# IR-Detector.net
KiCad netlist of a schematic drawn in Altium Designer
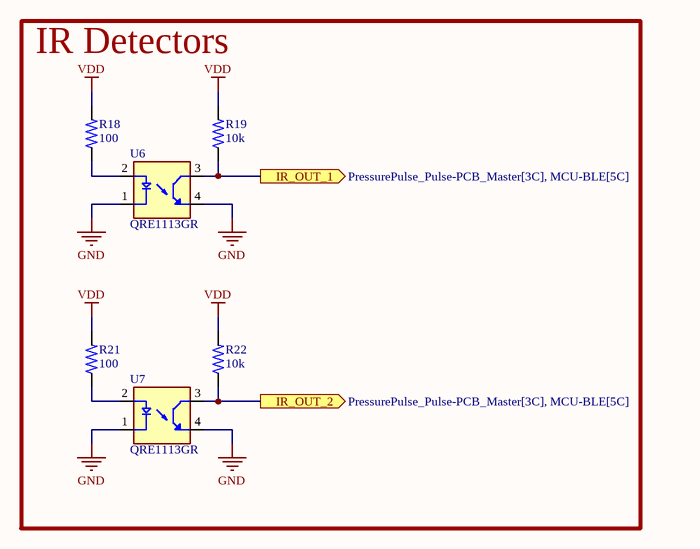
[diagram p0: IR-Detector.SchDoc]

(export (version "E")
  (design (tool "Eeschema 10.0.6"))
  (components
    (comp (ref "R18")
      (value "100")
      (footprint "PressurePulse:0402R")
      (description "Resistor")
      (fields (field (name "Comment") "RES"))
      (libsource (lib "PressurePulse") (part "RES"))
    )
    (comp (ref "R19")
      (value "10k")
      (footprint "PressurePulse:0402R")
      (description "Resistor")
      (fields (field (name "Comment") "RES"))
      (libsource (lib "PressurePulse") (part "RES"))
    )
    (comp (ref "R21")
      (value "100")
      (footprint "PressurePulse:0402R")
      (description "Resistor")
      (fields (field (name "Comment") "RES"))
      (libsource (lib "PressurePulse") (part "RES"))
    )
    (comp (ref "R22")
      (value "10k")
      (footprint "PressurePulse:0402R")
      (description "Resistor")
      (fields (field (name "Comment") "RES"))
      (libsource (lib "PressurePulse") (part "RES"))
    )
    (comp (ref "U6")
      (value "QRE1113GR")
      (footprint "PressurePulse:SMD-4P")
      (description "Reflective Optical Sensor 0.039 (1mm) 4-SMD, Gull Wing")
      (fields (field (name "MFR") "ON Semiconductor"))
      (libsource (lib "PressurePulse") (part "IR DETECTOR"))
    )
    (comp (ref "U7")
      (value "QRE1113GR")
      (footprint "PressurePulse:SMD-4P")
      (description "Reflective Optical Sensor 0.039 (1mm) 4-SMD, Gull Wing")
      (fields (field (name "MFR") "ON Semiconductor"))
      (libsource (lib "PressurePulse") (part "IR DETECTOR"))
    )
  )
  (nets
    (net (code "1") (name "/IR_OUT_1") (class "Default")
      (node (ref "R19") (pin "1") (pinfunction "1_1") (pintype "passive"))
      (node (ref "U6") (pin "3") (pinfunction "CT_3") (pintype "passive"))
    )
    (net (code "2") (name "/IR_OUT_2") (class "Default")
      (node (ref "R22") (pin "1") (pinfunction "1_1") (pintype "passive"))
      (node (ref "U7") (pin "3") (pinfunction "CT_3") (pintype "passive"))
    )
    (net (code "3") (name "GND") (class "Default")
      (node (ref "U6") (pin "1") (pinfunction "A_1") (pintype "passive"))
      (node (ref "U6") (pin "4") (pinfunction "ET_4") (pintype "passive"))
      (node (ref "U7") (pin "1") (pinfunction "A_1") (pintype "passive"))
      (node (ref "U7") (pin "4") (pinfunction "ET_4") (pintype "passive"))
    )
    (net (code "4") (name "Net-(U6-C)") (class "Default")
      (node (ref "R18") (pin "1") (pinfunction "1_1") (pintype "passive"))
      (node (ref "U6") (pin "2") (pinfunction "C_2") (pintype "passive"))
    )
    (net (code "5") (name "Net-(U7-C)") (class "Default")
      (node (ref "R21") (pin "1") (pinfunction "1_1") (pintype "passive"))
      (node (ref "U7") (pin "2") (pinfunction "C_2") (pintype "passive"))
    )
    (net (code "6") (name "VDD") (class "Default")
      (node (ref "R18") (pin "2") (pinfunction "2_2") (pintype "passive"))
      (node (ref "R19") (pin "2") (pinfunction "2_2") (pintype "passive"))
      (node (ref "R21") (pin "2") (pinfunction "2_2") (pintype "passive"))
      (node (ref "R22") (pin "2") (pinfunction "2_2") (pintype "passive"))
    )
  )
)
